# SCH_HackerCard_2024-08-26.net
KiCad netlist of a schematic drawn in EasyEDA
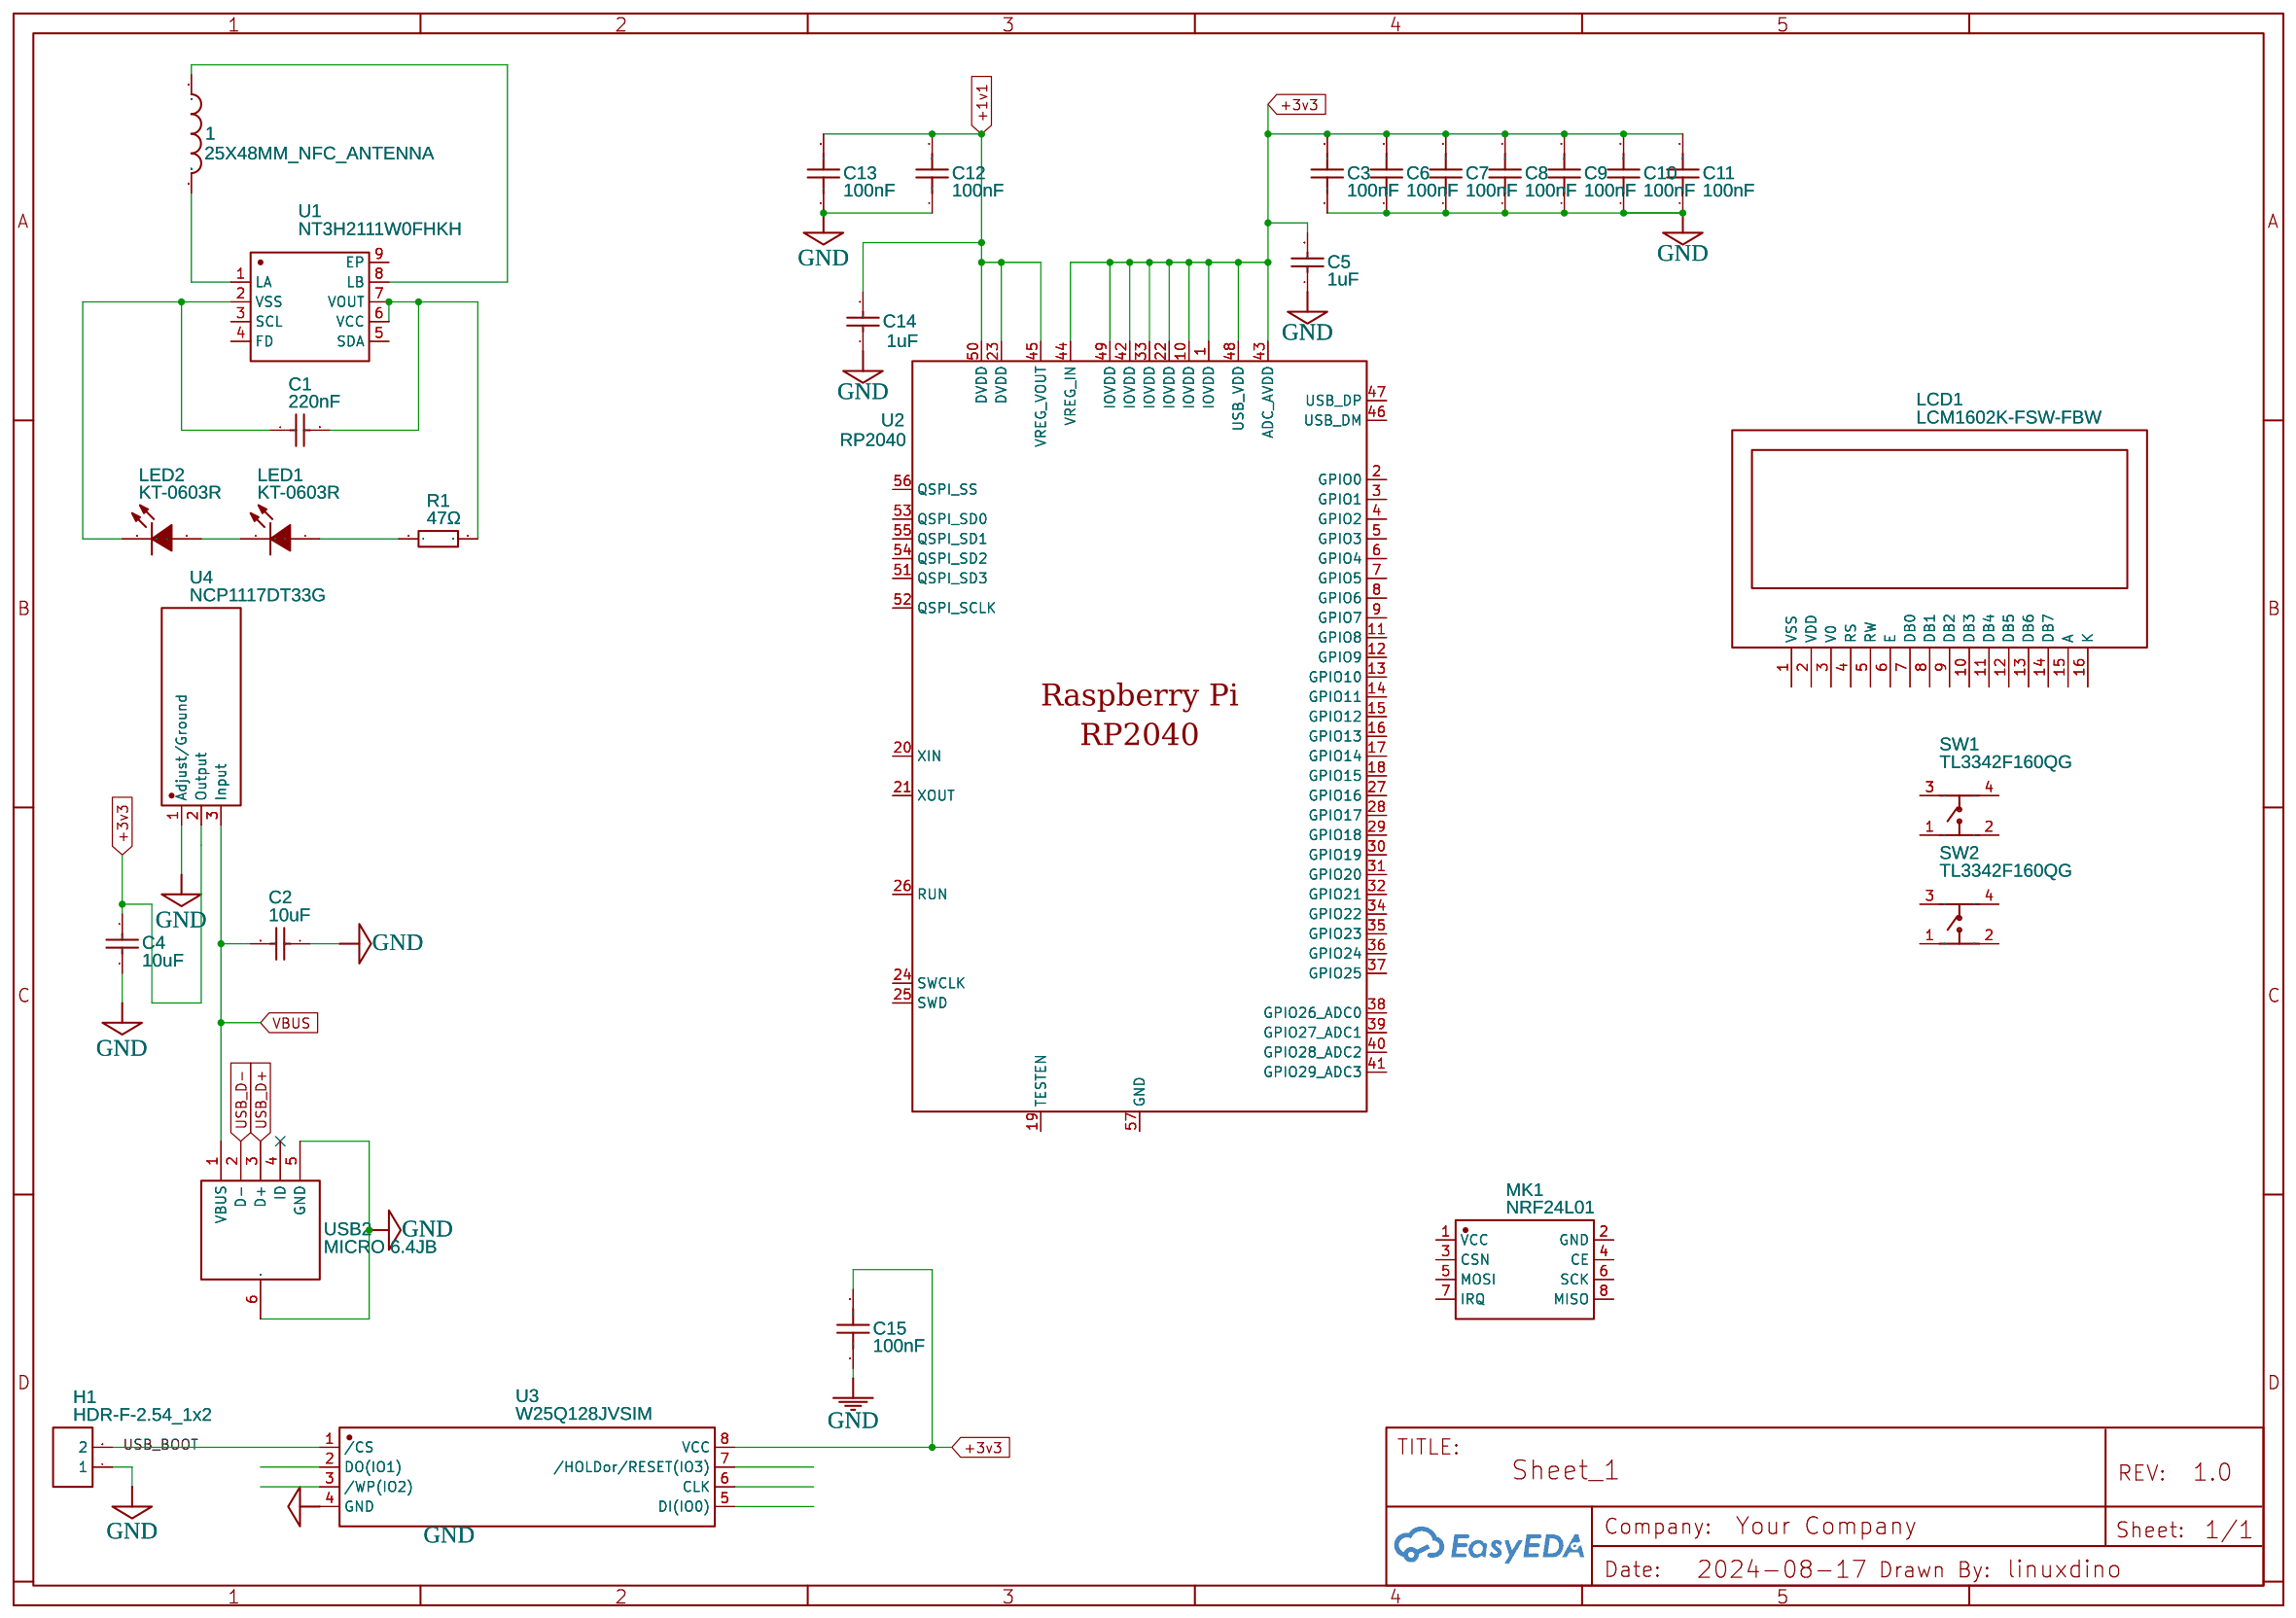
[diagram p0: schematic sheet]

(export (version "E")
  (design (tool "Eeschema 10.0.6"))
  (components
    (comp (ref "1") (value "25X48MM_NFC_ANTENNA") (libsource (lib "") (part "25X48MM_NFC_ANTENNA")))
    (comp (ref "C1")
      (value "220nF")
      (fields
        (field (name "Manufacturer Part") "CL10B224KA8NNNC")
        (field (name "Manufacturer") "SAMSUNG(三星)")
      )
      (libsource (lib "") (part "CL10B224KA8NNNC"))
    )
    (comp (ref "C2")
      (value "10uF")
      (fields
        (field (name "Manufacturer Part") "CL31A106KOHNNNE")
        (field (name "Manufacturer") "SAMSUNG(三星)")
      )
      (libsource (lib "") (part "CL31A106KOHNNNE"))
    )
    (comp (ref "C3")
      (value "100nF")
      (fields
        (field (name "Manufacturer Part") "CL10B104KB8NNNC")
        (field (name "Manufacturer") "SAMSUNG(三星)")
      )
      (libsource (lib "") (part "CL10B104KB8NNNC"))
    )
    (comp (ref "C4")
      (value "10uF")
      (fields
        (field (name "Manufacturer Part") "CL31A106KOHNNNE")
        (field (name "Manufacturer") "SAMSUNG(三星)")
      )
      (libsource (lib "") (part "CL31A106KOHNNNE_1"))
    )
    (comp (ref "C5")
      (value "1uF")
      (fields
        (field (name "Manufacturer Part") "CL10A105KO8NNNC")
        (field (name "Manufacturer") "SAMSUNG(三星)")
      )
      (libsource (lib "") (part "CL10A105KO8NNNC"))
    )
    (comp (ref "C6")
      (value "100nF")
      (fields
        (field (name "Manufacturer Part") "CL10B104KB8NNNC")
        (field (name "Manufacturer") "SAMSUNG(三星)")
      )
      (libsource (lib "") (part "CL10B104KB8NNNC"))
    )
    (comp (ref "C7")
      (value "100nF")
      (fields
        (field (name "Manufacturer Part") "CL10B104KB8NNNC")
        (field (name "Manufacturer") "SAMSUNG(三星)")
      )
      (libsource (lib "") (part "CL10B104KB8NNNC"))
    )
    (comp (ref "C8")
      (value "100nF")
      (fields
        (field (name "Manufacturer Part") "CL10B104KB8NNNC")
        (field (name "Manufacturer") "SAMSUNG(三星)")
      )
      (libsource (lib "") (part "CL10B104KB8NNNC"))
    )
    (comp (ref "C9")
      (value "100nF")
      (fields
        (field (name "Manufacturer Part") "CL10B104KB8NNNC")
        (field (name "Manufacturer") "SAMSUNG(三星)")
      )
      (libsource (lib "") (part "CL10B104KB8NNNC"))
    )
    (comp (ref "C10")
      (value "100nF")
      (fields
        (field (name "Manufacturer Part") "CL10B104KB8NNNC")
        (field (name "Manufacturer") "SAMSUNG(三星)")
      )
      (libsource (lib "") (part "CL10B104KB8NNNC"))
    )
    (comp (ref "C11")
      (value "100nF")
      (fields
        (field (name "Manufacturer Part") "CL10B104KB8NNNC")
        (field (name "Manufacturer") "SAMSUNG(三星)")
      )
      (libsource (lib "") (part "CL10B104KB8NNNC"))
    )
    (comp (ref "C12")
      (value "100nF")
      (fields
        (field (name "Manufacturer Part") "CL10B104KB8NNNC")
        (field (name "Manufacturer") "SAMSUNG(三星)")
      )
      (libsource (lib "") (part "CL10B104KB8NNNC"))
    )
    (comp (ref "C13")
      (value "100nF")
      (fields
        (field (name "Manufacturer Part") "CL10B104KB8NNNC")
        (field (name "Manufacturer") "SAMSUNG(三星)")
      )
      (libsource (lib "") (part "CL10B104KB8NNNC"))
    )
    (comp (ref "C14")
      (value "1uF")
      (fields
        (field (name "Manufacturer Part") "CL10A105KO8NNNC")
        (field (name "Manufacturer") "SAMSUNG(三星)")
      )
      (libsource (lib "") (part "CL10A105KO8NNNC"))
    )
    (comp (ref "C15")
      (value "100nF")
      (fields
        (field (name "Manufacturer Part") "CL10B104KB8NNNC")
        (field (name "Manufacturer") "SAMSUNG(三星)")
      )
      (libsource (lib "") (part "CL10B104KB8NNNC"))
    )
    (comp (ref "H1") (value "HDR-F-2.54_1x2") (libsource (lib "") (part "HDR-F-2.54_1x2")))
    (comp (ref "LCD1")
      (value "LCM1602K-FSW-FBW")
      (fields (field (name "Manufacturer") "LONTECH(厦门龙特)"))
      (libsource (lib "") (part "LCM1602K-FSW-FBW"))
    )
    (comp (ref "LED1")
      (value "KT-0603R")
      (fields (field (name "Manufacturer") "KENTO"))
      (libsource (lib "") (part "KT-0603R"))
    )
    (comp (ref "LED2")
      (value "KT-0603R")
      (fields (field (name "Manufacturer") "KENTO"))
      (libsource (lib "") (part "KT-0603R"))
    )
    (comp (ref "MK1")
      (value "NRF24L01")
      (fields (field (name "Manufacturer Part") "NF-04") (field (name "Manufacturer") "Ai-Thinker(安信可)"))
      (libsource (lib "") (part "NRF24L01"))
    )
    (comp (ref "R1")
      (value "47Ω")
      (fields
        (field (name "Manufacturer Part") "0603WAF470JT5E")
        (field (name "Manufacturer") "UNI-ROYAL(厚声)")
      )
      (libsource (lib "") (part "0603WAF470JT5E"))
    )
    (comp (ref "SW1")
      (value "TL3342F160QG")
      (fields (field (name "Manufacturer") "E-Switch"))
      (libsource (lib "") (part "TL3342F160QG"))
    )
    (comp (ref "SW2")
      (value "TL3342F160QG")
      (fields (field (name "Manufacturer") "E-Switch"))
      (libsource (lib "") (part "TL3342F160QG"))
    )
    (comp (ref "U1")
      (value "NT3H2111W0FHKH")
      (fields (field (name "Manufacturer") "NXP(恩智浦)"))
      (libsource (lib "") (part "NT3H2111W0FHKH"))
    )
    (comp (ref "U2")
      (value "RP2040")
      (fields (field (name "Manufacturer") "Raspberry Pi(树莓派)"))
      (libsource (lib "") (part "RP2040"))
    )
    (comp (ref "U3")
      (value "W25Q128JVSIM")
      (fields (field (name "Manufacturer") "WINBOND(华邦)"))
      (libsource (lib "") (part "W25Q128JVSIM"))
    )
    (comp (ref "U4")
      (value "NCP1117DT33G")
      (fields (field (name "Manufacturer") "onsemi(安森美)"))
      (libsource (lib "") (part "NCP1117DT33G"))
    )
    (comp (ref "USB2")
      (value "MICRO 6.4JB")
      (fields (field (name "Manufacturer") "SHOU HAN(首韩)"))
      (libsource (lib "") (part "MICRO 6.4JB"))
    )
  )
  (nets
    (net (code "1") (name "+1v1") (class "Default")
      (node (ref "C12") (pin "2") (pinfunction "2_2") (pintype "unspecified"))
      (node (ref "C13") (pin "2") (pinfunction "2_2") (pintype "unspecified"))
      (node (ref "C14") (pin "2") (pinfunction "2_2") (pintype "input"))
      (node (ref "U2") (pin "23") (pinfunction "DVDD_23") (pintype "bidirectional"))
      (node (ref "U2") (pin "45") (pinfunction "VREG_VOUT_45") (pintype "bidirectional"))
      (node (ref "U2") (pin "50") (pinfunction "DVDD_50") (pintype "bidirectional"))
    )
    (net (code "2") (name "+3v3") (class "Default")
      (node (ref "C10") (pin "2") (pinfunction "2_2") (pintype "unspecified"))
      (node (ref "C11") (pin "2") (pinfunction "2_2") (pintype "unspecified"))
      (node (ref "C15") (pin "2") (pinfunction "2_2") (pintype "unspecified"))
      (node (ref "C3") (pin "2") (pinfunction "2_2") (pintype "unspecified"))
      (node (ref "C4") (pin "2") (pinfunction "2_2") (pintype "input"))
      (node (ref "C5") (pin "2") (pinfunction "2_2") (pintype "input"))
      (node (ref "C6") (pin "2") (pinfunction "2_2") (pintype "unspecified"))
      (node (ref "C7") (pin "2") (pinfunction "2_2") (pintype "unspecified"))
      (node (ref "C8") (pin "2") (pinfunction "2_2") (pintype "unspecified"))
      (node (ref "C9") (pin "2") (pinfunction "2_2") (pintype "unspecified"))
      (node (ref "U2") (pin "1") (pinfunction "IOVDD_1") (pintype "bidirectional"))
      (node (ref "U2") (pin "10") (pinfunction "IOVDD_10") (pintype "bidirectional"))
      (node (ref "U2") (pin "22") (pinfunction "IOVDD_22") (pintype "bidirectional"))
      (node (ref "U2") (pin "33") (pinfunction "IOVDD_33") (pintype "bidirectional"))
      (node (ref "U2") (pin "42") (pinfunction "IOVDD_42") (pintype "bidirectional"))
      (node (ref "U2") (pin "43") (pinfunction "ADC_AVDD_43") (pintype "bidirectional"))
      (node (ref "U2") (pin "44") (pinfunction "VREG_IN_44") (pintype "bidirectional"))
      (node (ref "U2") (pin "48") (pinfunction "USB_VDD_48") (pintype "bidirectional"))
      (node (ref "U2") (pin "49") (pinfunction "IOVDD_49") (pintype "bidirectional"))
      (node (ref "U3") (pin "8") (pinfunction "VCC_8") (pintype "unspecified"))
      (node (ref "U4") (pin "2") (pinfunction "Output_2") (pintype "unspecified"))
    )
    (net (code "3") (name "/USB_BOOT") (class "Default")
      (node (ref "H1") (pin "2") (pinfunction "2_2") (pintype "input"))
      (node (ref "U3") (pin "1") (pinfunction "/CS_1") (pintype "unspecified"))
    )
    (net (code "4") (name "GND") (class "Default")
      (node (ref "C10") (pin "1") (pinfunction "1_1") (pintype "unspecified"))
      (node (ref "C11") (pin "1") (pinfunction "1_1") (pintype "unspecified"))
      (node (ref "C12") (pin "1") (pinfunction "1_1") (pintype "unspecified"))
      (node (ref "C13") (pin "1") (pinfunction "1_1") (pintype "unspecified"))
      (node (ref "C14") (pin "1") (pinfunction "1_1") (pintype "input"))
      (node (ref "C15") (pin "1") (pinfunction "1_1") (pintype "unspecified"))
      (node (ref "C2") (pin "1") (pinfunction "1_1") (pintype "input"))
      (node (ref "C3") (pin "1") (pinfunction "1_1") (pintype "unspecified"))
      (node (ref "C4") (pin "1") (pinfunction "1_1") (pintype "input"))
      (node (ref "C5") (pin "1") (pinfunction "1_1") (pintype "input"))
      (node (ref "C6") (pin "1") (pinfunction "1_1") (pintype "unspecified"))
      (node (ref "C7") (pin "1") (pinfunction "1_1") (pintype "unspecified"))
      (node (ref "C8") (pin "1") (pinfunction "1_1") (pintype "unspecified"))
      (node (ref "C9") (pin "1") (pinfunction "1_1") (pintype "unspecified"))
      (node (ref "H1") (pin "1") (pinfunction "1_1") (pintype "input"))
      (node (ref "U3") (pin "4") (pinfunction "GND_4") (pintype "unspecified"))
      (node (ref "U4") (pin "1") (pinfunction "Adjust/Ground_1") (pintype "unspecified"))
      (node (ref "USB2") (pin "5") (pinfunction "GND_5") (pintype "input"))
      (node (ref "USB2") (pin "6") (pinfunction "EH_6") (pintype "input"))
    )
    (net (code "5") (name "Net-(LED1-A)") (class "Default")
      (node (ref "LED1") (pin "2") (pinfunction "A_2") (pintype "unspecified"))
      (node (ref "R1") (pin "1") (pinfunction "1_1") (pintype "input"))
    )
    (net (code "6") (name "Net-(LED1-K)") (class "Default")
      (node (ref "LED1") (pin "1") (pinfunction "K_1") (pintype "unspecified"))
      (node (ref "LED2") (pin "2") (pinfunction "A_2") (pintype "unspecified"))
    )
    (net (code "7") (name "Net-(LED2-K)") (class "Default")
      (node (ref "C1") (pin "1") (pinfunction "1_1") (pintype "input"))
      (node (ref "LED2") (pin "1") (pinfunction "K_1") (pintype "unspecified"))
      (node (ref "U1") (pin "2") (pinfunction "VSS_2") (pintype "unspecified"))
    )
    (net (code "8") (name "Net-(U1-LA)") (class "Default")
      (node (ref "1") (pin "P$2") (pinfunction "P$2_P$2") (pintype "bidirectional"))
      (node (ref "U1") (pin "1") (pinfunction "LA_1") (pintype "unspecified"))
    )
    (net (code "9") (name "Net-(U1-LB)") (class "Default")
      (node (ref "1") (pin "P$1") (pinfunction "P$1_P$1") (pintype "bidirectional"))
      (node (ref "U1") (pin "8") (pinfunction "LB_8") (pintype "unspecified"))
    )
    (net (code "10") (name "Net-(U1-VCC)") (class "Default")
      (node (ref "C1") (pin "2") (pinfunction "2_2") (pintype "input"))
      (node (ref "R1") (pin "2") (pinfunction "2_2") (pintype "input"))
      (node (ref "U1") (pin "6") (pinfunction "VCC_6") (pintype "unspecified"))
      (node (ref "U1") (pin "7") (pinfunction "VOUT_7") (pintype "unspecified"))
    )
    (net (code "11") (name "USB_D+") (class "Default")
      (node (ref "USB2") (pin "3") (pinfunction "D+_3") (pintype "input"))
    )
    (net (code "12") (name "USB_D-") (class "Default")
      (node (ref "USB2") (pin "2") (pinfunction "D-_2") (pintype "input"))
    )
    (net (code "13") (name "VBUS") (class "Default")
      (node (ref "C2") (pin "2") (pinfunction "2_2") (pintype "input"))
      (node (ref "U4") (pin "3") (pinfunction "Input_3") (pintype "unspecified"))
      (node (ref "USB2") (pin "1") (pinfunction "VBUS_1") (pintype "input"))
    )
    (net (code "14") (name "unconnected-(LCD1-A-Pad15)") (class "Default")
      (node (ref "LCD1") (pin "15") (pinfunction "A_15") (pintype "unspecified"))
    )
    (net (code "15") (name "unconnected-(LCD1-DB0-Pad7)") (class "Default")
      (node (ref "LCD1") (pin "7") (pinfunction "DB0_7") (pintype "unspecified"))
    )
    (net (code "16") (name "unconnected-(LCD1-DB1-Pad8)") (class "Default")
      (node (ref "LCD1") (pin "8") (pinfunction "DB1_8") (pintype "unspecified"))
    )
    (net (code "17") (name "unconnected-(LCD1-DB2-Pad9)") (class "Default")
      (node (ref "LCD1") (pin "9") (pinfunction "DB2_9") (pintype "unspecified"))
    )
    (net (code "18") (name "unconnected-(LCD1-DB3-Pad10)") (class "Default")
      (node (ref "LCD1") (pin "10") (pinfunction "DB3_10") (pintype "unspecified"))
    )
    (net (code "19") (name "unconnected-(LCD1-DB4-Pad11)") (class "Default")
      (node (ref "LCD1") (pin "11") (pinfunction "DB4_11") (pintype "unspecified"))
    )
    (net (code "20") (name "unconnected-(LCD1-DB5-Pad12)") (class "Default")
      (node (ref "LCD1") (pin "12") (pinfunction "DB5_12") (pintype "unspecified"))
    )
    (net (code "21") (name "unconnected-(LCD1-DB6-Pad13)") (class "Default")
      (node (ref "LCD1") (pin "13") (pinfunction "DB6_13") (pintype "unspecified"))
    )
    (net (code "22") (name "unconnected-(LCD1-DB7-Pad14)") (class "Default")
      (node (ref "LCD1") (pin "14") (pinfunction "DB7_14") (pintype "unspecified"))
    )
    (net (code "23") (name "unconnected-(LCD1-E-Pad6)") (class "Default")
      (node (ref "LCD1") (pin "6") (pinfunction "E_6") (pintype "unspecified"))
    )
    (net (code "24") (name "unconnected-(LCD1-K-Pad16)") (class "Default")
      (node (ref "LCD1") (pin "16") (pinfunction "K_16") (pintype "unspecified"))
    )
    (net (code "25") (name "unconnected-(LCD1-RS-Pad4)") (class "Default")
      (node (ref "LCD1") (pin "4") (pinfunction "RS_4") (pintype "unspecified"))
    )
    (net (code "26") (name "unconnected-(LCD1-RW-Pad5)") (class "Default")
      (node (ref "LCD1") (pin "5") (pinfunction "RW_5") (pintype "unspecified"))
    )
    (net (code "27") (name "unconnected-(LCD1-V0-Pad3)") (class "Default")
      (node (ref "LCD1") (pin "3") (pinfunction "V0_3") (pintype "unspecified"))
    )
    (net (code "28") (name "unconnected-(LCD1-VDD-Pad2)") (class "Default")
      (node (ref "LCD1") (pin "2") (pinfunction "VDD_2") (pintype "unspecified"))
    )
    (net (code "29") (name "unconnected-(LCD1-VSS-Pad1)") (class "Default")
      (node (ref "LCD1") (pin "1") (pinfunction "VSS_1") (pintype "unspecified"))
    )
    (net (code "30") (name "unconnected-(MK1-CE-Pad4)") (class "Default")
      (node (ref "MK1") (pin "4") (pinfunction "CE_4") (pintype "unspecified"))
    )
    (net (code "31") (name "unconnected-(MK1-CSN-Pad3)") (class "Default")
      (node (ref "MK1") (pin "3") (pinfunction "CSN_3") (pintype "unspecified"))
    )
    (net (code "32") (name "unconnected-(MK1-GND-Pad2)") (class "Default")
      (node (ref "MK1") (pin "2") (pinfunction "GND_2") (pintype "unspecified"))
    )
    (net (code "33") (name "unconnected-(MK1-IRQ-Pad7)") (class "Default")
      (node (ref "MK1") (pin "7") (pinfunction "IRQ_7") (pintype "unspecified"))
    )
    (net (code "34") (name "unconnected-(MK1-MISO-Pad8)") (class "Default")
      (node (ref "MK1") (pin "8") (pinfunction "MISO_8") (pintype "unspecified"))
    )
    (net (code "35") (name "unconnected-(MK1-MOSI-Pad5)") (class "Default")
      (node (ref "MK1") (pin "5") (pinfunction "MOSI_5") (pintype "unspecified"))
    )
    (net (code "36") (name "unconnected-(MK1-SCK-Pad6)") (class "Default")
      (node (ref "MK1") (pin "6") (pinfunction "SCK_6") (pintype "unspecified"))
    )
    (net (code "37") (name "unconnected-(MK1-VCC-Pad1)") (class "Default")
      (node (ref "MK1") (pin "1") (pinfunction "VCC_1") (pintype "unspecified"))
    )
    (net (code "38") (name "unconnected-(SW1-Pad1)") (class "Default")
      (node (ref "SW1") (pin "1") (pinfunction "1_1") (pintype "unspecified"))
    )
    (net (code "39") (name "unconnected-(SW1-Pad2)") (class "Default")
      (node (ref "SW1") (pin "2") (pinfunction "2_2") (pintype "unspecified"))
    )
    (net (code "40") (name "unconnected-(SW1-Pad3)") (class "Default")
      (node (ref "SW1") (pin "3") (pinfunction "3_3") (pintype "unspecified"))
    )
    (net (code "41") (name "unconnected-(SW1-Pad4)") (class "Default")
      (node (ref "SW1") (pin "4") (pinfunction "4_4") (pintype "unspecified"))
    )
    (net (code "42") (name "unconnected-(SW2-Pad1)") (class "Default")
      (node (ref "SW2") (pin "1") (pinfunction "1_1") (pintype "unspecified"))
    )
    (net (code "43") (name "unconnected-(SW2-Pad2)") (class "Default")
      (node (ref "SW2") (pin "2") (pinfunction "2_2") (pintype "unspecified"))
    )
    (net (code "44") (name "unconnected-(SW2-Pad3)") (class "Default")
      (node (ref "SW2") (pin "3") (pinfunction "3_3") (pintype "unspecified"))
    )
    (net (code "45") (name "unconnected-(SW2-Pad4)") (class "Default")
      (node (ref "SW2") (pin "4") (pinfunction "4_4") (pintype "unspecified"))
    )
    (net (code "46") (name "unconnected-(U1-EP-Pad9)") (class "Default")
      (node (ref "U1") (pin "9") (pinfunction "EP_9") (pintype "unspecified"))
    )
    (net (code "47") (name "unconnected-(U1-FD-Pad4)") (class "Default")
      (node (ref "U1") (pin "4") (pinfunction "FD_4") (pintype "unspecified"))
    )
    (net (code "48") (name "unconnected-(U1-SCL-Pad3)") (class "Default")
      (node (ref "U1") (pin "3") (pinfunction "SCL_3") (pintype "unspecified"))
    )
    (net (code "49") (name "unconnected-(U1-SDA-Pad5)") (class "Default")
      (node (ref "U1") (pin "5") (pinfunction "SDA_5") (pintype "unspecified"))
    )
    (net (code "50") (name "unconnected-(U2-GND-Pad57)") (class "Default")
      (node (ref "U2") (pin "57") (pinfunction "GND_57") (pintype "bidirectional"))
    )
    (net (code "51") (name "unconnected-(U2-GPIO0-Pad2)") (class "Default")
      (node (ref "U2") (pin "2") (pinfunction "GPIO0_2") (pintype "bidirectional"))
    )
    (net (code "52") (name "unconnected-(U2-GPIO1-Pad3)") (class "Default")
      (node (ref "U2") (pin "3") (pinfunction "GPIO1_3") (pintype "bidirectional"))
    )
    (net (code "53") (name "unconnected-(U2-GPIO2-Pad4)") (class "Default")
      (node (ref "U2") (pin "4") (pinfunction "GPIO2_4") (pintype "bidirectional"))
    )
    (net (code "54") (name "unconnected-(U2-GPIO3-Pad5)") (class "Default")
      (node (ref "U2") (pin "5") (pinfunction "GPIO3_5") (pintype "bidirectional"))
    )
    (net (code "55") (name "unconnected-(U2-GPIO4-Pad6)") (class "Default")
      (node (ref "U2") (pin "6") (pinfunction "GPIO4_6") (pintype "bidirectional"))
    )
    (net (code "56") (name "unconnected-(U2-GPIO5-Pad7)") (class "Default")
      (node (ref "U2") (pin "7") (pinfunction "GPIO5_7") (pintype "bidirectional"))
    )
    (net (code "57") (name "unconnected-(U2-GPIO6-Pad8)") (class "Default")
      (node (ref "U2") (pin "8") (pinfunction "GPIO6_8") (pintype "bidirectional"))
    )
    (net (code "58") (name "unconnected-(U2-GPIO7-Pad9)") (class "Default")
      (node (ref "U2") (pin "9") (pinfunction "GPIO7_9") (pintype "bidirectional"))
    )
    (net (code "59") (name "unconnected-(U2-GPIO8-Pad11)") (class "Default")
      (node (ref "U2") (pin "11") (pinfunction "GPIO8_11") (pintype "bidirectional"))
    )
    (net (code "60") (name "unconnected-(U2-GPIO9-Pad12)") (class "Default")
      (node (ref "U2") (pin "12") (pinfunction "GPIO9_12") (pintype "bidirectional"))
    )
    (net (code "61") (name "unconnected-(U2-GPIO10-Pad13)") (class "Default")
      (node (ref "U2") (pin "13") (pinfunction "GPIO10_13") (pintype "bidirectional"))
    )
    (net (code "62") (name "unconnected-(U2-GPIO11-Pad14)") (class "Default")
      (node (ref "U2") (pin "14") (pinfunction "GPIO11_14") (pintype "bidirectional"))
    )
    (net (code "63") (name "unconnected-(U2-GPIO12-Pad15)") (class "Default")
      (node (ref "U2") (pin "15") (pinfunction "GPIO12_15") (pintype "bidirectional"))
    )
    (net (code "64") (name "unconnected-(U2-GPIO13-Pad16)") (class "Default")
      (node (ref "U2") (pin "16") (pinfunction "GPIO13_16") (pintype "bidirectional"))
    )
    (net (code "65") (name "unconnected-(U2-GPIO14-Pad17)") (class "Default")
      (node (ref "U2") (pin "17") (pinfunction "GPIO14_17") (pintype "bidirectional"))
    )
    (net (code "66") (name "unconnected-(U2-GPIO15-Pad18)") (class "Default")
      (node (ref "U2") (pin "18") (pinfunction "GPIO15_18") (pintype "bidirectional"))
    )
    (net (code "67") (name "unconnected-(U2-GPIO16-Pad27)") (class "Default")
      (node (ref "U2") (pin "27") (pinfunction "GPIO16_27") (pintype "bidirectional"))
    )
    (net (code "68") (name "unconnected-(U2-GPIO17-Pad28)") (class "Default")
      (node (ref "U2") (pin "28") (pinfunction "GPIO17_28") (pintype "bidirectional"))
    )
    (net (code "69") (name "unconnected-(U2-GPIO18-Pad29)") (class "Default")
      (node (ref "U2") (pin "29") (pinfunction "GPIO18_29") (pintype "bidirectional"))
    )
    (net (code "70") (name "unconnected-(U2-GPIO19-Pad30)") (class "Default")
      (node (ref "U2") (pin "30") (pinfunction "GPIO19_30") (pintype "bidirectional"))
    )
    (net (code "71") (name "unconnected-(U2-GPIO20-Pad31)") (class "Default")
      (node (ref "U2") (pin "31") (pinfunction "GPIO20_31") (pintype "bidirectional"))
    )
    (net (code "72") (name "unconnected-(U2-GPIO21-Pad32)") (class "Default")
      (node (ref "U2") (pin "32") (pinfunction "GPIO21_32") (pintype "bidirectional"))
    )
    (net (code "73") (name "unconnected-(U2-GPIO22-Pad34)") (class "Default")
      (node (ref "U2") (pin "34") (pinfunction "GPIO22_34") (pintype "bidirectional"))
    )
    (net (code "74") (name "unconnected-(U2-GPIO23-Pad35)") (class "Default")
      (node (ref "U2") (pin "35") (pinfunction "GPIO23_35") (pintype "bidirectional"))
    )
    (net (code "75") (name "unconnected-(U2-GPIO24-Pad36)") (class "Default")
      (node (ref "U2") (pin "36") (pinfunction "GPIO24_36") (pintype "bidirectional"))
    )
    (net (code "76") (name "unconnected-(U2-GPIO25-Pad37)") (class "Default")
      (node (ref "U2") (pin "37") (pinfunction "GPIO25_37") (pintype "bidirectional"))
    )
    (net (code "77") (name "unconnected-(U2-GPIO26_ADC0-Pad38)") (class "Default")
      (node (ref "U2") (pin "38") (pinfunction "GPIO26_ADC0_38") (pintype "bidirectional"))
    )
    (net (code "78") (name "unconnected-(U2-GPIO27_ADC1-Pad39)") (class "Default")
      (node (ref "U2") (pin "39") (pinfunction "GPIO27_ADC1_39") (pintype "bidirectional"))
    )
    (net (code "79") (name "unconnected-(U2-GPIO28_ADC2-Pad40)") (class "Default")
      (node (ref "U2") (pin "40") (pinfunction "GPIO28_ADC2_40") (pintype "bidirectional"))
    )
    (net (code "80") (name "unconnected-(U2-GPIO29_ADC3-Pad41)") (class "Default")
      (node (ref "U2") (pin "41") (pinfunction "GPIO29_ADC3_41") (pintype "bidirectional"))
    )
    (net (code "81") (name "unconnected-(U2-QSPI_SCLK-Pad52)") (class "Default")
      (node (ref "U2") (pin "52") (pinfunction "QSPI_SCLK_52") (pintype "output"))
    )
    (net (code "82") (name "unconnected-(U2-QSPI_SD0-Pad53)") (class "Default")
      (node (ref "U2") (pin "53") (pinfunction "QSPI_SD0_53") (pintype "bidirectional"))
    )
    (net (code "83") (name "unconnected-(U2-QSPI_SD1-Pad55)") (class "Default")
      (node (ref "U2") (pin "55") (pinfunction "QSPI_SD1_55") (pintype "bidirectional"))
    )
    (net (code "84") (name "unconnected-(U2-QSPI_SD2-Pad54)") (class "Default")
      (node (ref "U2") (pin "54") (pinfunction "QSPI_SD2_54") (pintype "bidirectional"))
    )
    (net (code "85") (name "unconnected-(U2-QSPI_SD3-Pad51)") (class "Default")
      (node (ref "U2") (pin "51") (pinfunction "QSPI_SD3_51") (pintype "bidirectional"))
    )
    (net (code "86") (name "unconnected-(U2-QSPI_SS-Pad56)") (class "Default")
      (node (ref "U2") (pin "56") (pinfunction "QSPI_SS_56") (pintype "bidirectional"))
    )
    (net (code "87") (name "unconnected-(U2-RUN-Pad26)") (class "Default")
      (node (ref "U2") (pin "26") (pinfunction "RUN_26") (pintype "input"))
    )
    (net (code "88") (name "unconnected-(U2-SWCLK-Pad24)") (class "Default")
      (node (ref "U2") (pin "24") (pinfunction "SWCLK_24") (pintype "output"))
    )
    (net (code "89") (name "unconnected-(U2-SWD-Pad25)") (class "Default")
      (node (ref "U2") (pin "25") (pinfunction "SWD_25") (pintype "bidirectional"))
    )
    (net (code "90") (name "unconnected-(U2-TESTEN-Pad19)") (class "Default")
      (node (ref "U2") (pin "19") (pinfunction "TESTEN_19") (pintype "unspecified"))
    )
    (net (code "91") (name "unconnected-(U2-USB_DM-Pad46)") (class "Default")
      (node (ref "U2") (pin "46") (pinfunction "USB_DM_46") (pintype "bidirectional"))
    )
    (net (code "92") (name "unconnected-(U2-USB_DP-Pad47)") (class "Default")
      (node (ref "U2") (pin "47") (pinfunction "USB_DP_47") (pintype "bidirectional"))
    )
    (net (code "93") (name "unconnected-(U2-XIN-Pad20)") (class "Default")
      (node (ref "U2") (pin "20") (pinfunction "XIN_20") (pintype "input"))
    )
    (net (code "94") (name "unconnected-(U2-XOUT-Pad21)") (class "Default")
      (node (ref "U2") (pin "21") (pinfunction "XOUT_21") (pintype "unspecified"))
    )
    (net (code "95") (name "unconnected-(U3-CLK-Pad6)") (class "Default")
      (node (ref "U3") (pin "6") (pinfunction "CLK_6") (pintype "unspecified"))
    )
    (net (code "96") (name "unconnected-(U3-DI(IO0)-Pad5)") (class "Default")
      (node (ref "U3") (pin "5") (pinfunction "DI(IO0)_5") (pintype "unspecified"))
    )
    (net (code "97") (name "unconnected-(U3-DO(IO1)-Pad2)") (class "Default")
      (node (ref "U3") (pin "2") (pinfunction "DO(IO1)_2") (pintype "unspecified"))
    )
    (net (code "98") (name "unconnected-(U3-{slash}HOLDor{slash}RESET(IO3)-Pad7)") (class "Default")
      (node (ref "U3") (pin "7") (pinfunction "/HOLDor/RESET(IO3)_7") (pintype "unspecified"))
    )
    (net (code "99") (name "unconnected-(U3-{slash}WP(IO2)-Pad3)") (class "Default")
      (node (ref "U3") (pin "3") (pinfunction "/WP(IO2)_3") (pintype "unspecified"))
    )
    (net (code "100") (name "unconnected-(USB2-ID-Pad4)") (class "Default")
      (node (ref "USB2") (pin "4") (pinfunction "ID_4") (pintype "input+no_connect"))
    )
  )
)
